# aeg_driver.net
KiCad netlist of a schematic drawn in EAGLE
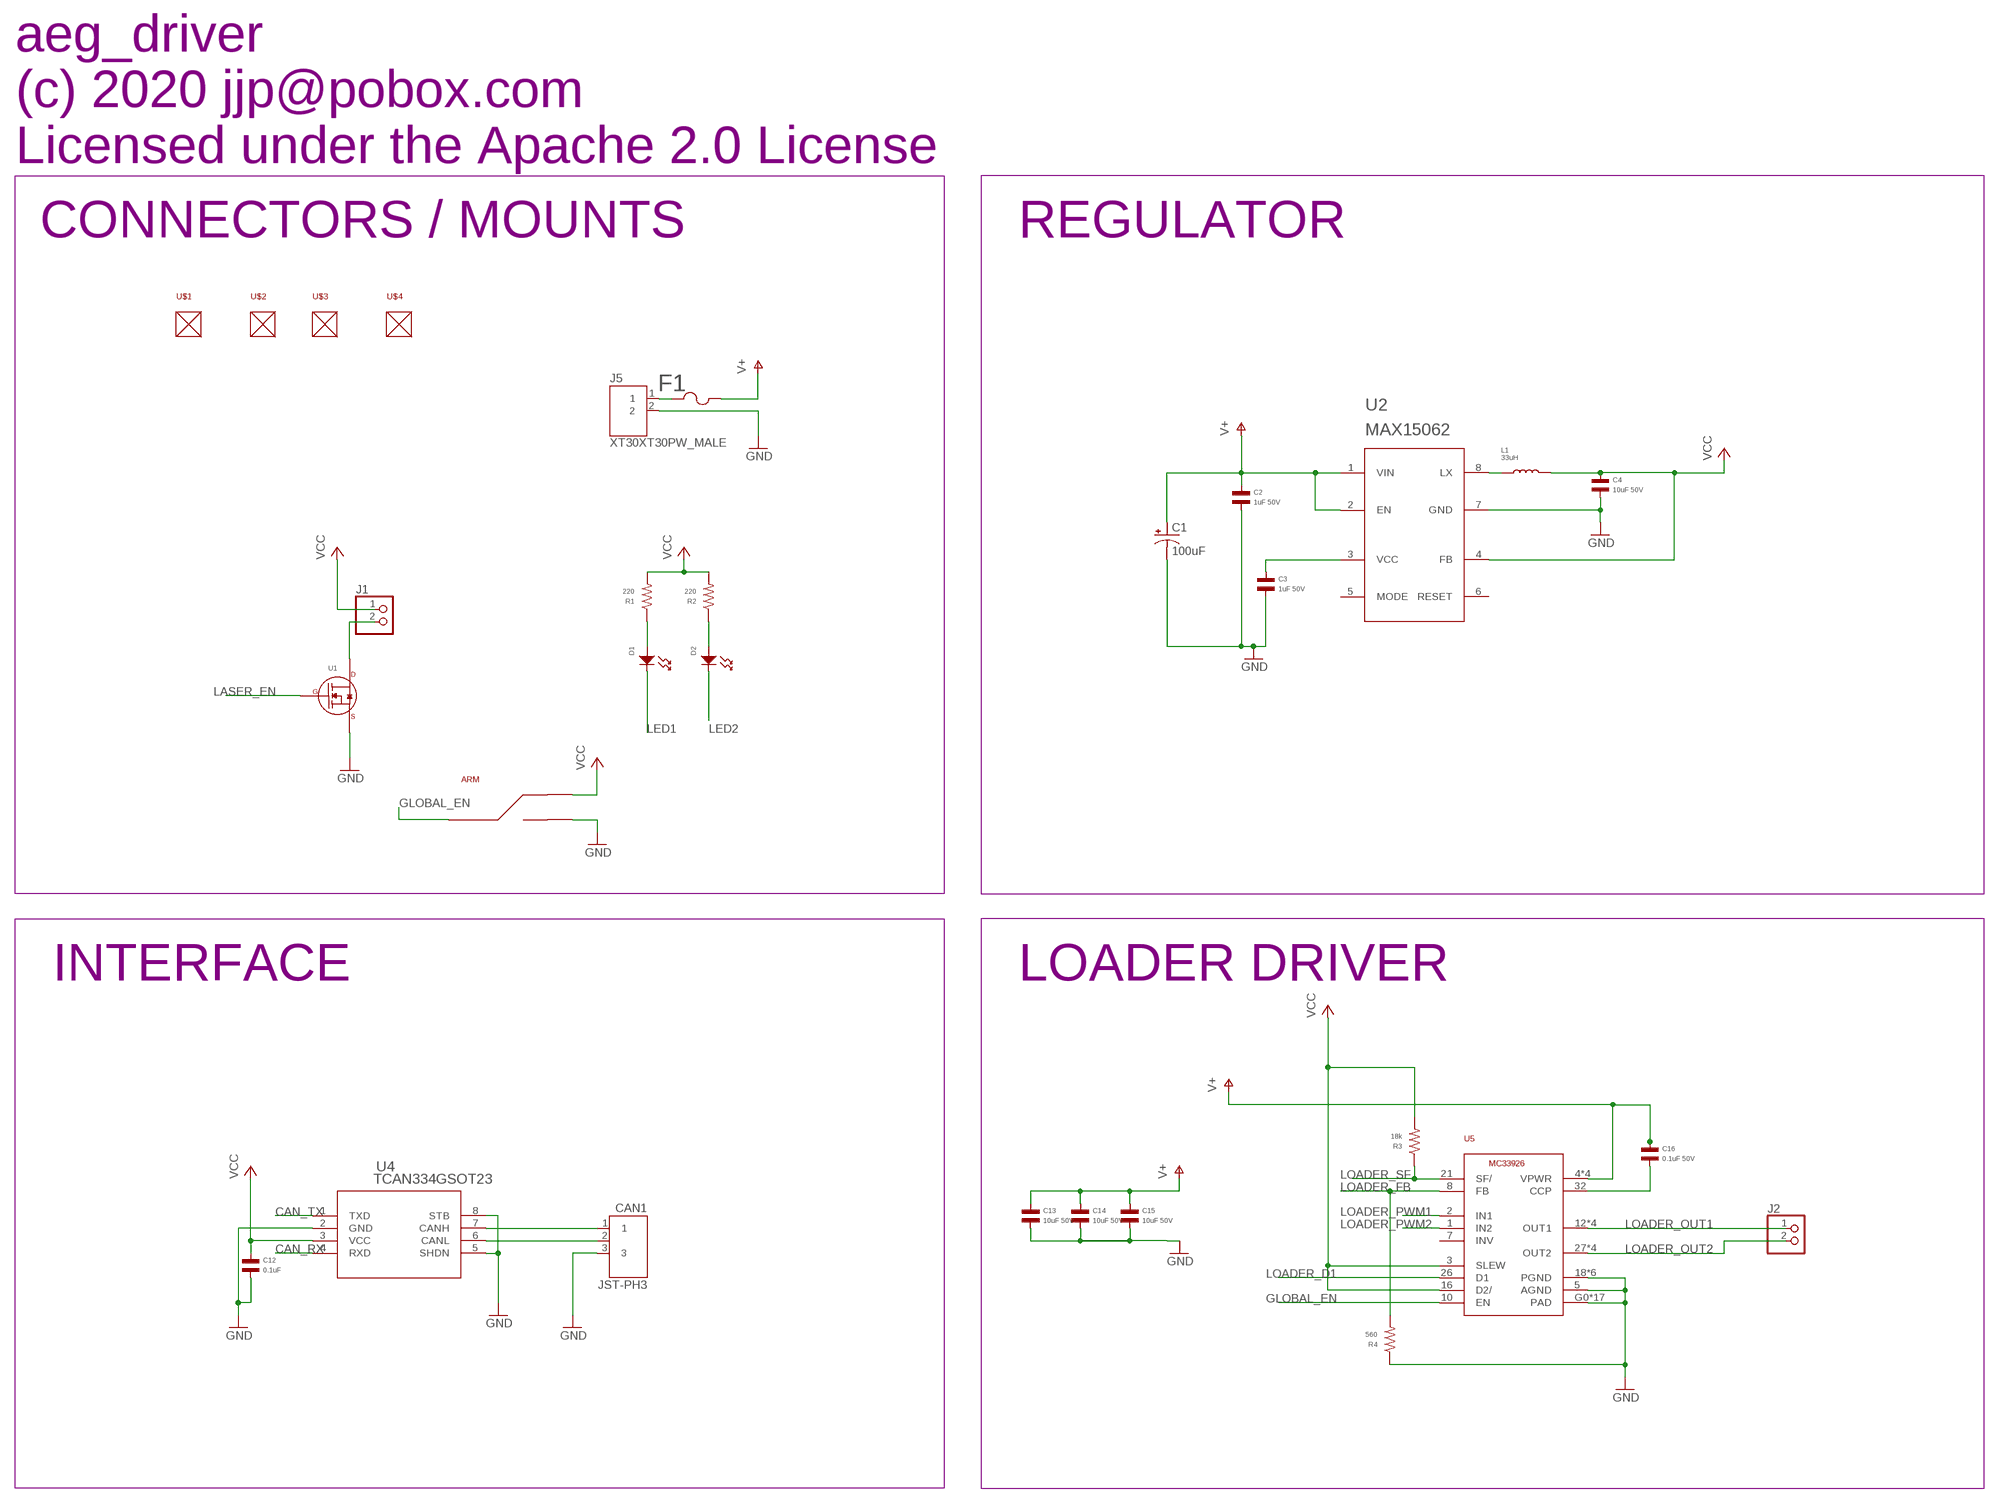
[diagram p0: schematic, sheet 1, part 1 of 2]
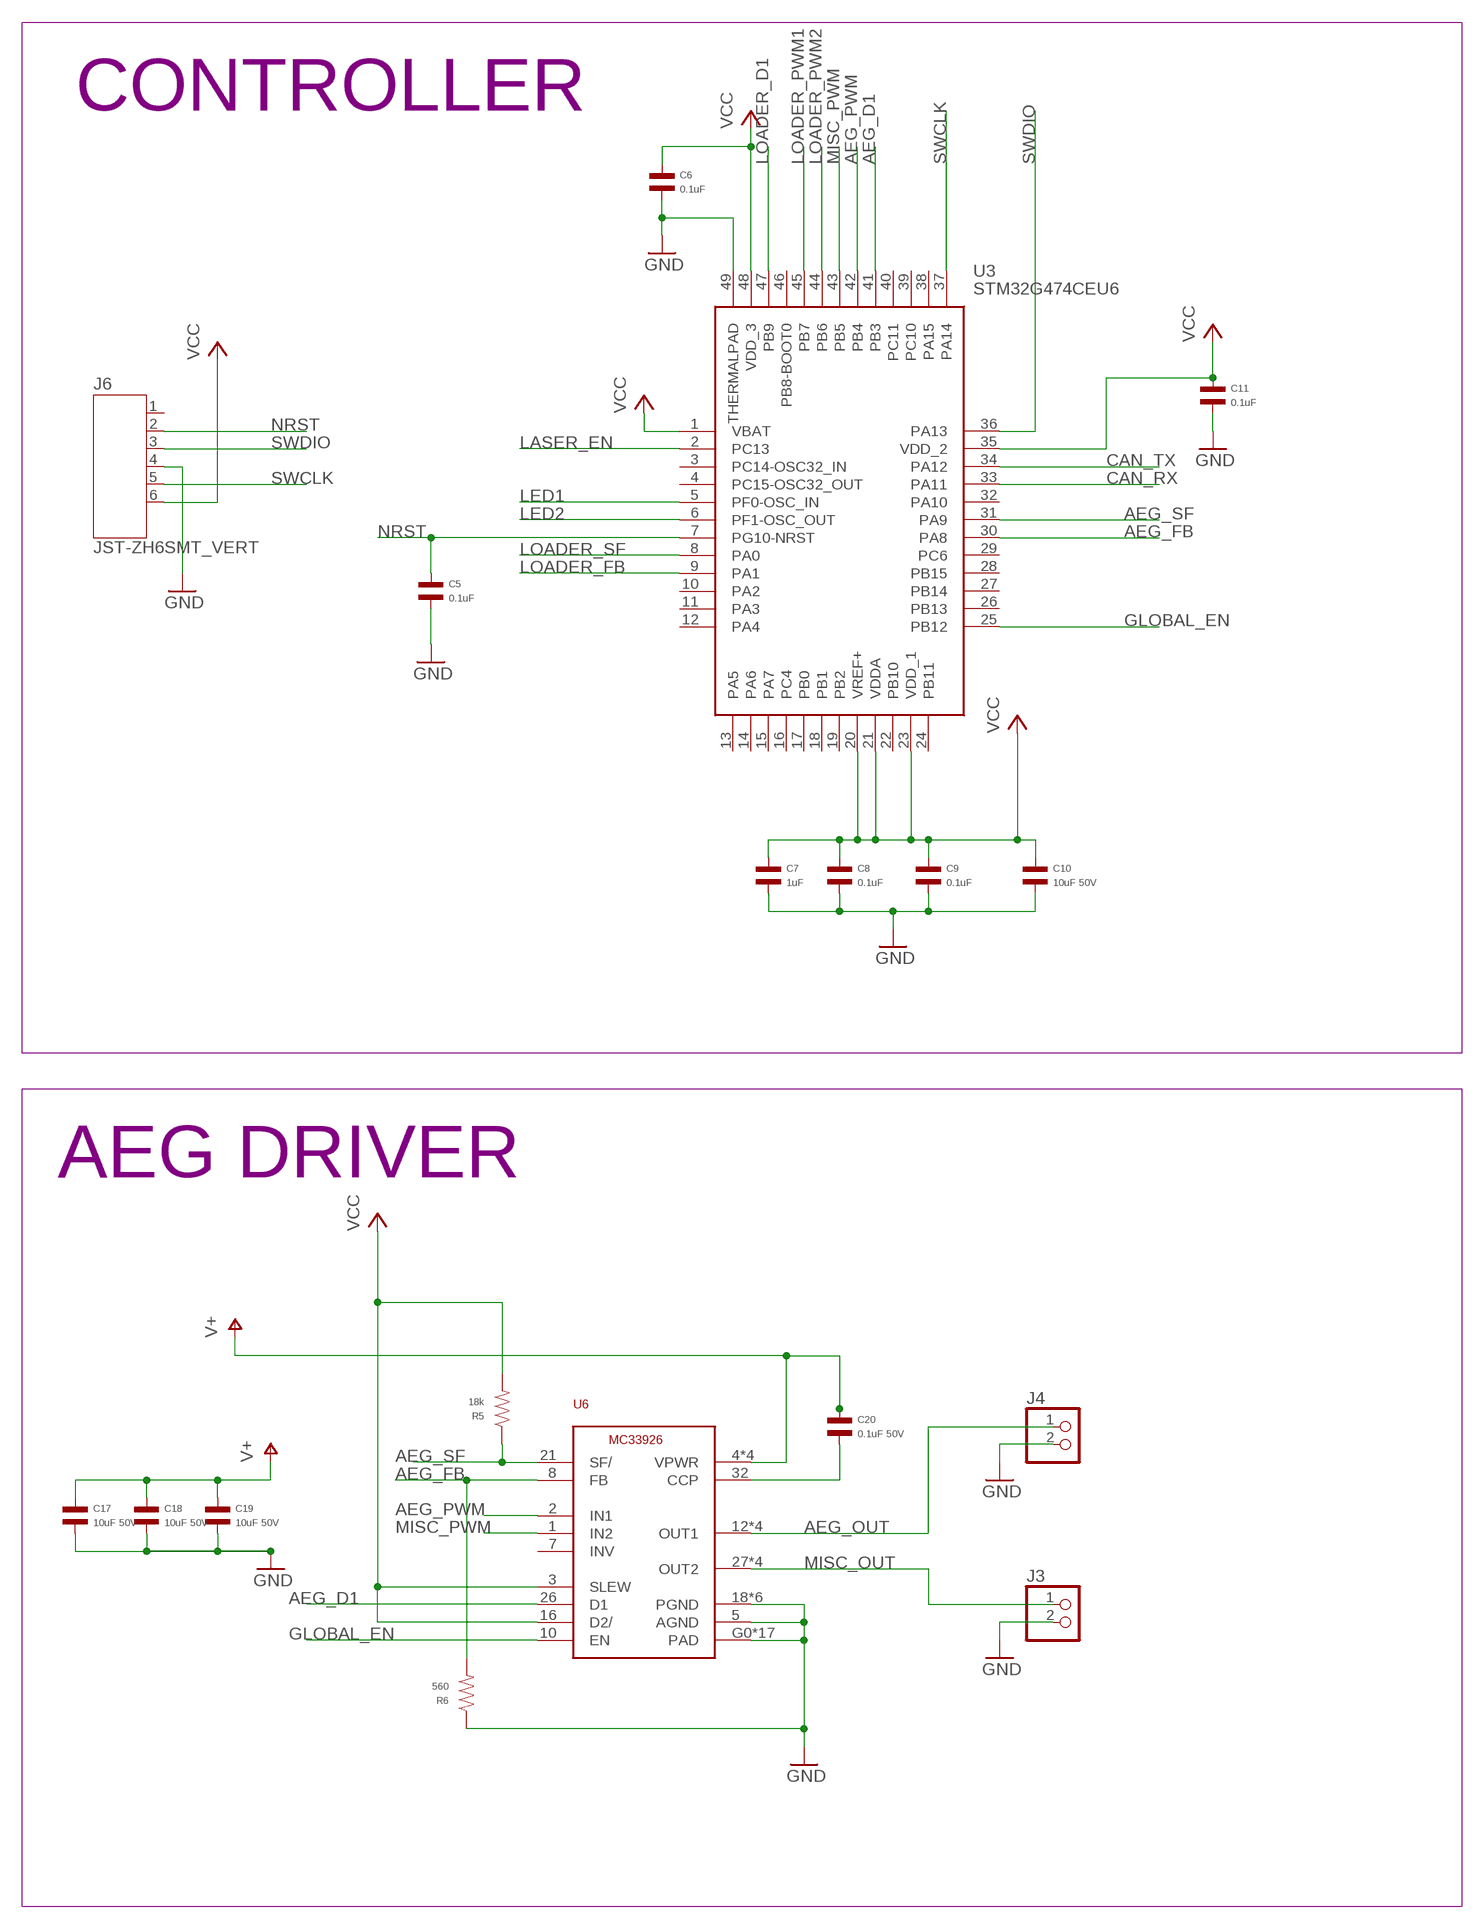
[diagram p1: schematic, sheet 1, part 2 of 2]

(export (version "E")
  (design (tool "Eeschema 10.0.6"))
  (components
    (comp (ref "ARM")
      (value "SLIDE_SWITCHJS_SUB_SWITCH")
      (footprint "eagle-import:JS_SUB_SWITCH")
      (fields (field (name "MPN") "JS102011SAQN"))
      (libsource (lib "eagle-import") (part "SLIDE_SWITCHJS_SUB_SWITCH"))
    )
    (comp (ref "C1")
      (value "100uF")
      (footprint "eagle-import:PANASONIC_FT_CAP_D")
      (fields (field (name "MF") "PANASONIC") (field (name "MPN") "EEE-FT1V101AP"))
      (libsource (lib "eagle-import") (part "CPOL-USFT_D"))
    )
    (comp (ref "C2")
      (value "1uF 50V")
      (footprint "eagle-import:C0603")
      (fields (field (name "MF") "SAMSUNG") (field (name "MPN") "CL10A105KB8NNNC"))
      (libsource (lib "eagle-import") (part "CAPACITOR_NP_0603"))
    )
    (comp (ref "C3")
      (value "1uF 50V")
      (footprint "eagle-import:C0603")
      (fields (field (name "MF") "SAMSUNG") (field (name "MPN") "CL10A105KB8NNNC"))
      (libsource (lib "eagle-import") (part "CAPACITOR_NP_0603"))
    )
    (comp (ref "C4")
      (value "10uF 50V")
      (footprint "eagle-import:C1206")
      (fields (field (name "MF") "TDK") (field (name "MPN") "C3216X7R1H106K160AE"))
      (libsource (lib "eagle-import") (part "CAPACITOR_NP_1206"))
    )
    (comp (ref "C5")
      (value "0.1uF")
      (footprint "eagle-import:C0402")
      (fields (field (name "HOUSEPART") "YES") (field (name "MPN") "MF-CAP-0402-0.1uF"))
      (libsource (lib "eagle-import") (part "CAPACITOR_NP_0402"))
    )
    (comp (ref "C6")
      (value "0.1uF")
      (footprint "eagle-import:C0402")
      (fields (field (name "HOUSEPART") "YES") (field (name "MPN") "MF-CAP-0402-0.1uF"))
      (libsource (lib "eagle-import") (part "CAPACITOR_NP_0402"))
    )
    (comp (ref "C7")
      (value "1uF")
      (footprint "eagle-import:C0402")
      (fields (field (name "HOUSEPART") "YES") (field (name "MPN") "MF-CAP-0402-1uF"))
      (libsource (lib "eagle-import") (part "CAPACITOR_NP_0402"))
    )
    (comp (ref "C8")
      (value "0.1uF")
      (footprint "eagle-import:C0402")
      (fields (field (name "HOUSEPART") "YES") (field (name "MPN") "MF-CAP-0402-0.1uF"))
      (libsource (lib "eagle-import") (part "CAPACITOR_NP_0402"))
    )
    (comp (ref "C9")
      (value "0.1uF")
      (footprint "eagle-import:C0402")
      (fields (field (name "HOUSEPART") "YES") (field (name "MPN") "MF-CAP-0402-0.1uF"))
      (libsource (lib "eagle-import") (part "CAPACITOR_NP_0402"))
    )
    (comp (ref "C10")
      (value "10uF 50V")
      (footprint "eagle-import:C1206")
      (fields (field (name "MF") "TDK") (field (name "MPN") "C3216X7R1H106K160AE"))
      (libsource (lib "eagle-import") (part "CAPACITOR_NP_1206"))
    )
    (comp (ref "C11")
      (value "0.1uF")
      (footprint "eagle-import:C0402")
      (fields (field (name "HOUSEPART") "YES") (field (name "MPN") "MF-CAP-0402-0.1uF"))
      (libsource (lib "eagle-import") (part "CAPACITOR_NP_0402"))
    )
    (comp (ref "C12")
      (value "0.1uF")
      (footprint "eagle-import:C0402")
      (fields (field (name "HOUSEPART") "YES") (field (name "MPN") "MF-CAP-0402-0.1uF"))
      (libsource (lib "eagle-import") (part "CAPACITOR_NP_0402"))
    )
    (comp (ref "C13")
      (value "10uF 50V")
      (footprint "eagle-import:C1206")
      (fields (field (name "MF") "TDK") (field (name "MPN") "C3216X7R1H106K160AE"))
      (libsource (lib "eagle-import") (part "CAPACITOR_NP_1206"))
    )
    (comp (ref "C14")
      (value "10uF 50V")
      (footprint "eagle-import:C1206")
      (fields (field (name "MF") "TDK") (field (name "MPN") "C3216X7R1H106K160AE"))
      (libsource (lib "eagle-import") (part "CAPACITOR_NP_1206"))
    )
    (comp (ref "C15")
      (value "10uF 50V")
      (footprint "eagle-import:C1206")
      (fields (field (name "MF") "TDK") (field (name "MPN") "C3216X7R1H106K160AE"))
      (libsource (lib "eagle-import") (part "CAPACITOR_NP_1206"))
    )
    (comp (ref "C16")
      (value "0.1uF 50V")
      (footprint "eagle-import:C0402")
      (fields (field (name "MF") "Walsin") (field (name "MPN") "0402B104K500CT"))
      (libsource (lib "eagle-import") (part "CAPACITOR_NP_0402"))
    )
    (comp (ref "C17")
      (value "10uF 50V")
      (footprint "eagle-import:C1206")
      (fields (field (name "MF") "TDK") (field (name "MPN") "C3216X7R1H106K160AE"))
      (libsource (lib "eagle-import") (part "CAPACITOR_NP_1206"))
    )
    (comp (ref "C18")
      (value "10uF 50V")
      (footprint "eagle-import:C1206")
      (fields (field (name "MF") "TDK") (field (name "MPN") "C3216X7R1H106K160AE"))
      (libsource (lib "eagle-import") (part "CAPACITOR_NP_1206"))
    )
    (comp (ref "C19")
      (value "10uF 50V")
      (footprint "eagle-import:C1206")
      (fields (field (name "MF") "TDK") (field (name "MPN") "C3216X7R1H106K160AE"))
      (libsource (lib "eagle-import") (part "CAPACITOR_NP_1206"))
    )
    (comp (ref "C20")
      (value "0.1uF 50V")
      (footprint "eagle-import:C0402")
      (fields (field (name "MF") "Walsin") (field (name "MPN") "0402B104K500CT"))
      (libsource (lib "eagle-import") (part "CAPACITOR_NP_0402"))
    )
    (comp (ref "CAN1")
      (value "JST-PH3")
      (footprint "eagle-import:JST_S3B-PH-SM4-TB(LF)(SN)")
      (fields (field (name "MF") "JST") (field (name "MPN") "S3B-PH-SM4-TB(LF)(SN)"))
      (libsource (lib "eagle-import") (part "JST-PH3"))
    )
    (comp (ref "D1")
      (value "LED_SINGLE-0603-RED")
      (footprint "eagle-import:LED0603")
      (fields (field (name "HOUSEPART") "YES") (field (name "MPN") "MF-LED-0603-RED"))
      (libsource (lib "eagle-import") (part "LED_SINGLE-0603-RED"))
    )
    (comp (ref "D2")
      (value "LED_SINGLE-0603-RED")
      (footprint "eagle-import:LED0603")
      (fields
        (field (name "HOUSEPART") "YES")
        (field (name "MPN") "MF-LED-0603-RED")
        (field (name "MPN_1") "MF-LED-0603-GREEN")
      )
      (libsource (lib "eagle-import") (part "LED_SINGLE-0603-RED"))
    )
    (comp (ref "F1")
      (value "MFU0603FF04000P100")
      (footprint "eagle-import:FUS_VISHAY_MFU0603")
      (fields (field (name "MF") "VISHAY"))
      (libsource (lib "eagle-import") (part "MFU0603FF04000P100"))
    )
    (comp (ref "J1")
      (value "PINHD-1X2")
      (footprint "eagle-import:1X02")
      (libsource (lib "eagle-import") (part "PINHD-1X2"))
    )
    (comp (ref "J2")
      (value "PINHD-1X2")
      (footprint "eagle-import:1X02")
      (libsource (lib "eagle-import") (part "PINHD-1X2"))
    )
    (comp (ref "J3")
      (value "PINHD-1X2")
      (footprint "eagle-import:1X02")
      (libsource (lib "eagle-import") (part "PINHD-1X2"))
    )
    (comp (ref "J4")
      (value "PINHD-1X2")
      (footprint "eagle-import:1X02")
      (libsource (lib "eagle-import") (part "PINHD-1X2"))
    )
    (comp (ref "J5")
      (value "XT30XT30PW_MALE")
      (footprint "eagle-import:XT30PW_MALE")
      (fields (field (name "MPN") "XT30PW-M"))
      (libsource (lib "eagle-import") (part "XT30XT30PW_MALE"))
    )
    (comp (ref "J6")
      (value "JST-ZH6SMT_VERT")
      (footprint "eagle-import:JST_B6B-ZR-SM4-TF(LF)(SN)")
      (fields (field (name "MF") "JST") (field (name "MPN") "B6B-ZR-SM4-TF(LF)(SN)"))
      (libsource (lib "eagle-import") (part "JST-ZH6SMT_VERT"))
    )
    (comp (ref "L1")
      (value "33uH")
      (footprint "eagle-import:L1210")
      (fields (field (name "MF") "TDK") (field (name "MPN") "NLFV32T-330K-EF") (field (name "POPULATE") "1"))
      (libsource (lib "eagle-import") (part "INDUCTOR_1210"))
    )
    (comp (ref "R1")
      (value "220")
      (footprint "eagle-import:R0603")
      (fields (field (name "HOUSEPART") "YES") (field (name "MPN") "MF-RES-0603-220"))
      (libsource (lib "eagle-import") (part "RESISTOR_0603"))
    )
    (comp (ref "R2")
      (value "220")
      (footprint "eagle-import:R0603")
      (fields (field (name "HOUSEPART") "YES") (field (name "MPN") "MF-RES-0603-220"))
      (libsource (lib "eagle-import") (part "RESISTOR_0603"))
    )
    (comp (ref "R3")
      (value "18k")
      (footprint "eagle-import:R0603")
      (fields (field (name "HOUSEPART") "YES") (field (name "MPN") "MF-RES-0603-18K"))
      (libsource (lib "eagle-import") (part "RESISTOR_0603"))
    )
    (comp (ref "R4")
      (value "560")
      (footprint "eagle-import:R0603")
      (fields (field (name "HOUSEPART") "YES") (field (name "MPN") "MF-RES-0603-560"))
      (libsource (lib "eagle-import") (part "RESISTOR_0603"))
    )
    (comp (ref "R5")
      (value "18k")
      (footprint "eagle-import:R0603")
      (fields (field (name "HOUSEPART") "YES") (field (name "MPN") "MF-RES-0603-18K"))
      (libsource (lib "eagle-import") (part "RESISTOR_0603"))
    )
    (comp (ref "R6")
      (value "560")
      (footprint "eagle-import:R0603")
      (fields (field (name "HOUSEPART") "YES") (field (name "MPN") "MF-RES-0603-560"))
      (libsource (lib "eagle-import") (part "RESISTOR_0603"))
    )
    (comp (ref "U$1")
      (value "MOUNT")
      (footprint "eagle-import:M2.5MOUNT")
      (libsource (lib "eagle-import") (part "MOUNT"))
    )
    (comp (ref "U$2")
      (value "MOUNT")
      (footprint "eagle-import:M2.5MOUNT")
      (libsource (lib "eagle-import") (part "MOUNT"))
    )
    (comp (ref "U$3")
      (value "MOUNT")
      (footprint "eagle-import:M2.5MOUNT")
      (libsource (lib "eagle-import") (part "MOUNT"))
    )
    (comp (ref "U$4")
      (value "MOUNT")
      (footprint "eagle-import:M2.5MOUNT")
      (libsource (lib "eagle-import") (part "MOUNT"))
    )
    (comp (ref "U1")
      (value "N-CHANNEL_FET_SOT-23-3")
      (footprint "eagle-import:SOT-23-3")
      (fields (field (name "HOUSEPART") "YES") (field (name "MPN") "MF-DSC-SOT233-BSS138"))
      (libsource (lib "eagle-import") (part "N-CHANNEL_FET_SOT-23-3"))
    )
    (comp (ref "U2")
      (value "MAX150628TDFN")
      (footprint "eagle-import:8TDFN")
      (fields (field (name "MF") "MAXIM") (field (name "MPN") "MAX15062AATA+T"))
      (libsource (lib "eagle-import") (part "MAX150628TDFN"))
    )
    (comp (ref "U3")
      (value "STM32G474CEU6")
      (footprint "eagle-import:QFN50P700X700X60-49N")
      (fields (field (name "MOUSER_PART_NUMBER") "511-STM32G474CEU6") (field (name "MF") "ST"))
      (libsource (lib "eagle-import") (part "STM32G474CEU6"))
    )
    (comp (ref "U4")
      (value "TCAN334GSOT23")
      (footprint "eagle-import:SOT23-8")
      (fields (field (name "MF") "TI") (field (name "MPN") "TCAN334GDCNT"))
      (libsource (lib "eagle-import") (part "TCAN334GSOT23"))
    )
    (comp (ref "U5")
      (value "MC33926")
      (footprint "eagle-import:PQFN32")
      (fields (field (name "MF") "Freescale") (field (name "MPN") "MC33926PNBR2"))
      (libsource (lib "eagle-import") (part "MC33926"))
    )
    (comp (ref "U6")
      (value "MC33926")
      (footprint "eagle-import:PQFN32")
      (fields (field (name "MF") "Freescale") (field (name "MPN") "MC33926PNBR2"))
      (libsource (lib "eagle-import") (part "MC33926"))
    )
  )
  (nets
    (net (code "1") (name "/AEG_D1") (class "Default")
      (node (ref "U3") (pin "41") (pinfunction "PB3_41") (pintype "bidirectional"))
      (node (ref "U6") (pin "26") (pinfunction "D1_26") (pintype "bidirectional"))
    )
    (net (code "2") (name "/AEG_FB") (class "Default")
      (node (ref "R6") (pin "P$2") (pinfunction "P$2_P$2") (pintype "passive"))
      (node (ref "U3") (pin "30") (pinfunction "PA8_30") (pintype "bidirectional"))
      (node (ref "U6") (pin "8") (pinfunction "FB_8") (pintype "bidirectional"))
    )
    (net (code "3") (name "/AEG_OUT") (class "Default")
      (node (ref "J4") (pin "1") (pinfunction "1_1") (pintype "passive"))
      (node (ref "U6") (pin "12") (pinfunction "OUT1_12") (pintype "bidirectional"))
      (node (ref "U6") (pin "13") (pinfunction "OUT1_13") (pintype "bidirectional"))
      (node (ref "U6") (pin "14") (pinfunction "OUT1_14") (pintype "bidirectional"))
      (node (ref "U6") (pin "15") (pinfunction "OUT1_15") (pintype "bidirectional"))
    )
    (net (code "4") (name "/AEG_PWM") (class "Default")
      (node (ref "U3") (pin "42") (pinfunction "PB4_42") (pintype "bidirectional"))
      (node (ref "U6") (pin "2") (pinfunction "IN1_2") (pintype "bidirectional"))
    )
    (net (code "5") (name "/AEG_SF") (class "Default")
      (node (ref "R5") (pin "P$1") (pinfunction "P$1_P$1") (pintype "passive"))
      (node (ref "U3") (pin "31") (pinfunction "PA9_31") (pintype "bidirectional"))
      (node (ref "U6") (pin "21") (pinfunction "SF/_21") (pintype "bidirectional"))
    )
    (net (code "6") (name "/CAN_RX") (class "Default")
      (node (ref "U3") (pin "33") (pinfunction "PA11_33") (pintype "bidirectional"))
      (node (ref "U4") (pin "4") (pinfunction "RXD_4") (pintype "output"))
    )
    (net (code "7") (name "/CAN_TX") (class "Default")
      (node (ref "U3") (pin "34") (pinfunction "PA12_34") (pintype "bidirectional"))
      (node (ref "U4") (pin "1") (pinfunction "TXD_1") (pintype "input"))
    )
    (net (code "8") (name "/GLOBAL_EN") (class "Default")
      (node (ref "ARM") (pin "2") (pinfunction "2_2") (pintype "bidirectional"))
      (node (ref "U3") (pin "25") (pinfunction "PB12_25") (pintype "bidirectional"))
      (node (ref "U5") (pin "10") (pinfunction "EN_10") (pintype "bidirectional"))
      (node (ref "U6") (pin "10") (pinfunction "EN_10") (pintype "bidirectional"))
    )
    (net (code "9") (name "/LASER_EN") (class "Default")
      (node (ref "U1") (pin "P$1") (pinfunction "GATE_P$1") (pintype "bidirectional"))
      (node (ref "U3") (pin "2") (pinfunction "PC13_2") (pintype "bidirectional"))
    )
    (net (code "10") (name "/LED1") (class "Default")
      (node (ref "D1") (pin "CATHODE") (pinfunction "CATHODE_CATHODE") (pintype "power_in"))
      (node (ref "U3") (pin "5") (pinfunction "PF0-OSC_IN_5") (pintype "bidirectional"))
    )
    (net (code "11") (name "/LED2") (class "Default")
      (node (ref "D2") (pin "CATHODE") (pinfunction "CATHODE_CATHODE") (pintype "power_in"))
      (node (ref "U3") (pin "6") (pinfunction "PF1-OSC_OUT_6") (pintype "bidirectional"))
    )
    (net (code "12") (name "/LOADER_D1") (class "Default")
      (node (ref "U3") (pin "47") (pinfunction "PB9_47") (pintype "bidirectional"))
      (node (ref "U5") (pin "26") (pinfunction "D1_26") (pintype "bidirectional"))
    )
    (net (code "13") (name "/LOADER_FB") (class "Default")
      (node (ref "R4") (pin "P$2") (pinfunction "P$2_P$2") (pintype "passive"))
      (node (ref "U3") (pin "9") (pinfunction "PA1_9") (pintype "bidirectional"))
      (node (ref "U5") (pin "8") (pinfunction "FB_8") (pintype "bidirectional"))
    )
    (net (code "14") (name "/LOADER_OUT1") (class "Default")
      (node (ref "J2") (pin "1") (pinfunction "1_1") (pintype "passive"))
      (node (ref "U5") (pin "12") (pinfunction "OUT1_12") (pintype "bidirectional"))
      (node (ref "U5") (pin "13") (pinfunction "OUT1_13") (pintype "bidirectional"))
      (node (ref "U5") (pin "14") (pinfunction "OUT1_14") (pintype "bidirectional"))
      (node (ref "U5") (pin "15") (pinfunction "OUT1_15") (pintype "bidirectional"))
    )
    (net (code "15") (name "/LOADER_OUT2") (class "Default")
      (node (ref "J2") (pin "2") (pinfunction "2_2") (pintype "passive"))
      (node (ref "U5") (pin "27") (pinfunction "OUT2_27") (pintype "bidirectional"))
      (node (ref "U5") (pin "28") (pinfunction "OUT2_28") (pintype "bidirectional"))
      (node (ref "U5") (pin "29") (pinfunction "OUT2_29") (pintype "bidirectional"))
      (node (ref "U5") (pin "30") (pinfunction "OUT2_30") (pintype "bidirectional"))
    )
    (net (code "16") (name "/LOADER_PWM1") (class "Default")
      (node (ref "U3") (pin "45") (pinfunction "PB7_45") (pintype "bidirectional"))
      (node (ref "U5") (pin "2") (pinfunction "IN1_2") (pintype "bidirectional"))
    )
    (net (code "17") (name "/LOADER_PWM2") (class "Default")
      (node (ref "U3") (pin "44") (pinfunction "PB6_44") (pintype "bidirectional"))
      (node (ref "U5") (pin "1") (pinfunction "IN2_1") (pintype "bidirectional"))
    )
    (net (code "18") (name "/LOADER_SF") (class "Default")
      (node (ref "R3") (pin "P$1") (pinfunction "P$1_P$1") (pintype "passive"))
      (node (ref "U3") (pin "8") (pinfunction "PA0_8") (pintype "bidirectional"))
      (node (ref "U5") (pin "21") (pinfunction "SF/_21") (pintype "bidirectional"))
    )
    (net (code "19") (name "/MISC_OUT") (class "Default")
      (node (ref "J3") (pin "1") (pinfunction "1_1") (pintype "passive"))
      (node (ref "U6") (pin "27") (pinfunction "OUT2_27") (pintype "bidirectional"))
      (node (ref "U6") (pin "28") (pinfunction "OUT2_28") (pintype "bidirectional"))
      (node (ref "U6") (pin "29") (pinfunction "OUT2_29") (pintype "bidirectional"))
      (node (ref "U6") (pin "30") (pinfunction "OUT2_30") (pintype "bidirectional"))
    )
    (net (code "20") (name "/MISC_PWM") (class "Default")
      (node (ref "U3") (pin "43") (pinfunction "PB5_43") (pintype "bidirectional"))
      (node (ref "U6") (pin "1") (pinfunction "IN2_1") (pintype "bidirectional"))
    )
    (net (code "21") (name "/NRST") (class "Default")
      (node (ref "C5") (pin "P$1") (pinfunction "P$1_P$1") (pintype "passive"))
      (node (ref "J6") (pin "2") (pinfunction "2_2") (pintype "passive"))
      (node (ref "U3") (pin "7") (pinfunction "PG10-NRST_7") (pintype "bidirectional"))
    )
    (net (code "22") (name "/SWCLK") (class "Default")
      (node (ref "J6") (pin "5") (pinfunction "5_5") (pintype "passive"))
      (node (ref "U3") (pin "37") (pinfunction "PA14_37") (pintype "bidirectional"))
    )
    (net (code "23") (name "/SWDIO") (class "Default")
      (node (ref "J6") (pin "3") (pinfunction "3_3") (pintype "passive"))
      (node (ref "U3") (pin "36") (pinfunction "PA13_36") (pintype "bidirectional"))
    )
    (net (code "24") (name "GND") (class "Default")
      (node (ref "ARM") (pin "3") (pinfunction "3_3") (pintype "bidirectional"))
      (node (ref "C1") (pin "-") (pinfunction "-_-") (pintype "passive"))
      (node (ref "C10") (pin "P$2") (pinfunction "P$2_P$2") (pintype "passive"))
      (node (ref "C11") (pin "P$2") (pinfunction "P$2_P$2") (pintype "passive"))
      (node (ref "C12") (pin "P$2") (pinfunction "P$2_P$2") (pintype "passive"))
      (node (ref "C13") (pin "P$2") (pinfunction "P$2_P$2") (pintype "passive"))
      (node (ref "C14") (pin "P$2") (pinfunction "P$2_P$2") (pintype "passive"))
      (node (ref "C15") (pin "P$2") (pinfunction "P$2_P$2") (pintype "passive"))
      (node (ref "C17") (pin "P$2") (pinfunction "P$2_P$2") (pintype "passive"))
      (node (ref "C18") (pin "P$2") (pinfunction "P$2_P$2") (pintype "passive"))
      (node (ref "C19") (pin "P$2") (pinfunction "P$2_P$2") (pintype "passive"))
      (node (ref "C2") (pin "P$2") (pinfunction "P$2_P$2") (pintype "passive"))
      (node (ref "C3") (pin "P$2") (pinfunction "P$2_P$2") (pintype "passive"))
      (node (ref "C4") (pin "P$2") (pinfunction "P$2_P$2") (pintype "passive"))
      (node (ref "C5") (pin "P$2") (pinfunction "P$2_P$2") (pintype "passive"))
      (node (ref "C6") (pin "P$2") (pinfunction "P$2_P$2") (pintype "passive"))
      (node (ref "C7") (pin "P$2") (pinfunction "P$2_P$2") (pintype "passive"))
      (node (ref "C8") (pin "P$2") (pinfunction "P$2_P$2") (pintype "passive"))
      (node (ref "C9") (pin "P$2") (pinfunction "P$2_P$2") (pintype "passive"))
      (node (ref "CAN1") (pin "3") (pinfunction "3_3") (pintype "passive"))
      (node (ref "J3") (pin "2") (pinfunction "2_2") (pintype "passive"))
      (node (ref "J4") (pin "2") (pinfunction "2_2") (pintype "passive"))
      (node (ref "J5") (pin "2") (pinfunction "2_2") (pintype "passive"))
      (node (ref "J6") (pin "4") (pinfunction "4_4") (pintype "passive"))
      (node (ref "R4") (pin "P$1") (pinfunction "P$1_P$1") (pintype "passive"))
      (node (ref "R6") (pin "P$1") (pinfunction "P$1_P$1") (pintype "passive"))
      (node (ref "U1") (pin "P$2") (pinfunction "SOURCE_P$2") (pintype "bidirectional"))
      (node (ref "U2") (pin "7") (pinfunction "GND_7") (pintype "passive"))
      (node (ref "U3") (pin "49") (pinfunction "THERMALPAD_49") (pintype "bidirectional"))
      (node (ref "U4") (pin "2") (pinfunction "GND_2") (pintype "power_in"))
      (node (ref "U4") (pin "5") (pinfunction "SHDN_5") (pintype "input"))
      (node (ref "U4") (pin "8") (pinfunction "STB_8") (pintype "input"))
      (node (ref "U5") (pin "18") (pinfunction "PGND_18") (pintype "bidirectional"))
      (node (ref "U5") (pin "19") (pinfunction "PGND_19") (pintype "bidirectional"))
      (node (ref "U5") (pin "20") (pinfunction "PGND_20") (pintype "bidirectional"))
      (node (ref "U5") (pin "22") (pinfunction "PGND_22") (pintype "bidirectional"))
      (node (ref "U5") (pin "23") (pinfunction "PGND_23") (pintype "bidirectional"))
      (node (ref "U5") (pin "24") (pinfunction "PGND_24") (pintype "bidirectional"))
      (node (ref "U5") (pin "5") (pinfunction "AGND_5") (pintype "bidirectional"))
      (node (ref "U5") (pin "G0") (pinfunction "PAD_G0") (pintype "bidirectional"))
      (node (ref "U5") (pin "G1") (pinfunction "PAD_G1") (pintype "bidirectional"))
      (node (ref "U5") (pin "G10") (pinfunction "PAD_G10") (pintype "bidirectional"))
      (node (ref "U5") (pin "G11") (pinfunction "PAD_G11") (pintype "bidirectional"))
      (node (ref "U5") (pin "G12") (pinfunction "PAD_G12") (pintype "bidirectional"))
      (node (ref "U5") (pin "G13") (pinfunction "PAD_G13") (pintype "bidirectional"))
      (node (ref "U5") (pin "G14") (pinfunction "PAD_G14") (pintype "bidirectional"))
      (node (ref "U5") (pin "G15") (pinfunction "PAD_G15") (pintype "bidirectional"))
      (node (ref "U5") (pin "G16") (pinfunction "PAD_G16") (pintype "bidirectional"))
      (node (ref "U5") (pin "G2") (pinfunction "PAD_G2") (pintype "bidirectional"))
      (node (ref "U5") (pin "G3") (pinfunction "PAD_G3") (pintype "bidirectional"))
      (node (ref "U5") (pin "G4") (pinfunction "PAD_G4") (pintype "bidirectional"))
      (node (ref "U5") (pin "G5") (pinfunction "PAD_G5") (pintype "bidirectional"))
      (node (ref "U5") (pin "G6") (pinfunction "PAD_G6") (pintype "bidirectional"))
      (node (ref "U5") (pin "G7") (pinfunction "PAD_G7") (pintype "bidirectional"))
      (node (ref "U5") (pin "G8") (pinfunction "PAD_G8") (pintype "bidirectional"))
      (node (ref "U5") (pin "G9") (pinfunction "PAD_G9") (pintype "bidirectional"))
      (node (ref "U6") (pin "18") (pinfunction "PGND_18") (pintype "bidirectional"))
      (node (ref "U6") (pin "19") (pinfunction "PGND_19") (pintype "bidirectional"))
      (node (ref "U6") (pin "20") (pinfunction "PGND_20") (pintype "bidirectional"))
      (node (ref "U6") (pin "22") (pinfunction "PGND_22") (pintype "bidirectional"))
      (node (ref "U6") (pin "23") (pinfunction "PGND_23") (pintype "bidirectional"))
      (node (ref "U6") (pin "24") (pinfunction "PGND_24") (pintype "bidirectional"))
      (node (ref "U6") (pin "5") (pinfunction "AGND_5") (pintype "bidirectional"))
      (node (ref "U6") (pin "G0") (pinfunction "PAD_G0") (pintype "bidirectional"))
      (node (ref "U6") (pin "G1") (pinfunction "PAD_G1") (pintype "bidirectional"))
      (node (ref "U6") (pin "G10") (pinfunction "PAD_G10") (pintype "bidirectional"))
      (node (ref "U6") (pin "G11") (pinfunction "PAD_G11") (pintype "bidirectional"))
      (node (ref "U6") (pin "G12") (pinfunction "PAD_G12") (pintype "bidirectional"))
      (node (ref "U6") (pin "G13") (pinfunction "PAD_G13") (pintype "bidirectional"))
      (node (ref "U6") (pin "G14") (pinfunction "PAD_G14") (pintype "bidirectional"))
      (node (ref "U6") (pin "G15") (pinfunction "PAD_G15") (pintype "bidirectional"))
      (node (ref "U6") (pin "G16") (pinfunction "PAD_G16") (pintype "bidirectional"))
      (node (ref "U6") (pin "G2") (pinfunction "PAD_G2") (pintype "bidirectional"))
      (node (ref "U6") (pin "G3") (pinfunction "PAD_G3") (pintype "bidirectional"))
      (node (ref "U6") (pin "G4") (pinfunction "PAD_G4") (pintype "bidirectional"))
      (node (ref "U6") (pin "G5") (pinfunction "PAD_G5") (pintype "bidirectional"))
      (node (ref "U6") (pin "G6") (pinfunction "PAD_G6") (pintype "bidirectional"))
      (node (ref "U6") (pin "G7") (pinfunction "PAD_G7") (pintype "bidirectional"))
      (node (ref "U6") (pin "G8") (pinfunction "PAD_G8") (pintype "bidirectional"))
      (node (ref "U6") (pin "G9") (pinfunction "PAD_G9") (pintype "bidirectional"))
    )
    (net (code "25") (name "Net-(D1-PadANODE)") (class "Default")
      (node (ref "D1") (pin "ANODE") (pinfunction "ANODE_ANODE") (pintype "power_in"))
      (node (ref "R1") (pin "P$1") (pinfunction "P$1_P$1") (pintype "passive"))
    )
    (net (code "26") (name "Net-(D2-PadANODE)") (class "Default")
      (node (ref "D2") (pin "ANODE") (pinfunction "ANODE_ANODE") (pintype "power_in"))
      (node (ref "R2") (pin "P$1") (pinfunction "P$1_P$1") (pintype "passive"))
    )
    (net (code "27") (name "Net-(F1-Pad1)") (class "Default")
      (node (ref "F1") (pin "1") (pinfunction "1_1") (pintype "passive"))
      (node (ref "J5") (pin "1") (pinfunction "1_1") (pintype "passive"))
    )
    (net (code "28") (name "Net-(U1-DRAIN)") (class "Default")
      (node (ref "J1") (pin "2") (pinfunction "2_2") (pintype "passive"))
      (node (ref "U1") (pin "P$3") (pinfunction "DRAIN_P$3") (pintype "bidirectional"))
    )
    (net (code "29") (name "Net-(U2-LX)") (class "Default")
      (node (ref "L1") (pin "P$1") (pinfunction "P$1_P$1") (pintype "passive"))
      (node (ref "U2") (pin "8") (pinfunction "LX_8") (pintype "passive"))
    )
    (net (code "30") (name "Net-(U2-VCC)") (class "Default")
      (node (ref "C3") (pin "P$1") (pinfunction "P$1_P$1") (pintype "passive"))
      (node (ref "U2") (pin "3") (pinfunction "VCC_3") (pintype "passive"))
    )
    (net (code "31") (name "Net-(U4-CANH)") (class "Default")
      (node (ref "CAN1") (pin "1") (pinfunction "1_1") (pintype "passive"))
      (node (ref "U4") (pin "7") (pinfunction "CANH_7") (pintype "bidirectional"))
    )
    (net (code "32") (name "Net-(U4-CANL)") (class "Default")
      (node (ref "CAN1") (pin "2") (pinfunction "2_2") (pintype "passive"))
      (node (ref "U4") (pin "6") (pinfunction "CANL_6") (pintype "bidirectional"))
    )
    (net (code "33") (name "Net-(U5-CCP)") (class "Default")
      (node (ref "C16") (pin "P$2") (pinfunction "P$2_P$2") (pintype "passive"))
      (node (ref "U5") (pin "32") (pinfunction "CCP_32") (pintype "bidirectional"))
    )
    (net (code "34") (name "Net-(U6-CCP)") (class "Default")
      (node (ref "C20") (pin "P$2") (pinfunction "P$2_P$2") (pintype "passive"))
      (node (ref "U6") (pin "32") (pinfunction "CCP_32") (pintype "bidirectional"))
    )
    (net (code "35") (name "V+") (class "Default")
      (node (ref "C1") (pin "+") (pinfunction "+_+") (pintype "passive"))
      (node (ref "C13") (pin "P$1") (pinfunction "P$1_P$1") (pintype "passive"))
      (node (ref "C14") (pin "P$1") (pinfunction "P$1_P$1") (pintype "passive"))
      (node (ref "C15") (pin "P$1") (pinfunction "P$1_P$1") (pintype "passive"))
      (node (ref "C16") (pin "P$1") (pinfunction "P$1_P$1") (pintype "passive"))
      (node (ref "C17") (pin "P$1") (pinfunction "P$1_P$1") (pintype "passive"))
      (node (ref "C18") (pin "P$1") (pinfunction "P$1_P$1") (pintype "passive"))
      (node (ref "C19") (pin "P$1") (pinfunction "P$1_P$1") (pintype "passive"))
      (node (ref "C2") (pin "P$1") (pinfunction "P$1_P$1") (pintype "passive"))
      (node (ref "C20") (pin "P$1") (pinfunction "P$1_P$1") (pintype "passive"))
      (node (ref "F1") (pin "2") (pinfunction "2_2") (pintype "passive"))
      (node (ref "U2") (pin "1") (pinfunction "VIN_1") (pintype "passive"))
      (node (ref "U2") (pin "2") (pinfunction "EN_2") (pintype "passive"))
      (node (ref "U5") (pin "11") (pinfunction "VPWR_11") (pintype "bidirectional"))
      (node (ref "U5") (pin "31") (pinfunction "VPWR_31") (pintype "bidirectional"))
      (node (ref "U5") (pin "4") (pinfunction "VPWR_4") (pintype "bidirectional"))
      (node (ref "U5") (pin "6") (pinfunction "VPWR_6") (pintype "bidirectional"))
      (node (ref "U6") (pin "11") (pinfunction "VPWR_11") (pintype "bidirectional"))
      (node (ref "U6") (pin "31") (pinfunction "VPWR_31") (pintype "bidirectional"))
      (node (ref "U6") (pin "4") (pinfunction "VPWR_4") (pintype "bidirectional"))
      (node (ref "U6") (pin "6") (pinfunction "VPWR_6") (pintype "bidirectional"))
    )
    (net (code "36") (name "VCC") (class "Default")
      (node (ref "ARM") (pin "1") (pinfunction "1_1") (pintype "bidirectional"))
      (node (ref "C10") (pin "P$1") (pinfunction "P$1_P$1") (pintype "passive"))
      (node (ref "C11") (pin "P$1") (pinfunction "P$1_P$1") (pintype "passive"))
      (node (ref "C12") (pin "P$1") (pinfunction "P$1_P$1") (pintype "passive"))
      (node (ref "C4") (pin "P$1") (pinfunction "P$1_P$1") (pintype "passive"))
      (node (ref "C6") (pin "P$1") (pinfunction "P$1_P$1") (pintype "passive"))
      (node (ref "C7") (pin "P$1") (pinfunction "P$1_P$1") (pintype "passive"))
      (node (ref "C8") (pin "P$1") (pinfunction "P$1_P$1") (pintype "passive"))
      (node (ref "C9") (pin "P$1") (pinfunction "P$1_P$1") (pintype "passive"))
      (node (ref "J1") (pin "1") (pinfunction "1_1") (pintype "passive"))
      (node (ref "J6") (pin "6") (pinfunction "6_6") (pintype "passive"))
      (node (ref "L1") (pin "P$2") (pinfunction "P$2_P$2") (pintype "passive"))
      (node (ref "R1") (pin "P$2") (pinfunction "P$2_P$2") (pintype "passive"))
      (node (ref "R2") (pin "P$2") (pinfunction "P$2_P$2") (pintype "passive"))
      (node (ref "R3") (pin "P$2") (pinfunction "P$2_P$2") (pintype "passive"))
      (node (ref "R5") (pin "P$2") (pinfunction "P$2_P$2") (pintype "passive"))
      (node (ref "U2") (pin "4") (pinfunction "FB_4") (pintype "passive"))
      (node (ref "U3") (pin "1") (pinfunction "VBAT_1") (pintype "bidirectional"))
      (node (ref "U3") (pin "20") (pinfunction "VREF+_20") (pintype "bidirectional"))
      (node (ref "U3") (pin "21") (pinfunction "VDDA_21") (pintype "bidirectional"))
      (node (ref "U3") (pin "23") (pinfunction "VDD_1_23") (pintype "bidirectional"))
      (node (ref "U3") (pin "35") (pinfunction "VDD_2_35") (pintype "bidirectional"))
      (node (ref "U3") (pin "48") (pinfunction "VDD_3_48") (pintype "bidirectional"))
      (node (ref "U4") (pin "3") (pinfunction "VCC_3") (pintype "power_in"))
      (node (ref "U5") (pin "16") (pinfunction "D2/_16") (pintype "bidirectional"))
      (node (ref "U5") (pin "3") (pinfunction "SLEW_3") (pintype "bidirectional"))
      (node (ref "U6") (pin "16") (pinfunction "D2/_16") (pintype "bidirectional"))
      (node (ref "U6") (pin "3") (pinfunction "SLEW_3") (pintype "bidirectional"))
    )
    (net (code "37") (name "unconnected-(J6-Pad1)") (class "Default")
      (node (ref "J6") (pin "1") (pinfunction "1_1") (pintype "passive"))
    )
    (net (code "38") (name "unconnected-(U2-MODE-Pad5)") (class "Default")
      (node (ref "U2") (pin "5") (pinfunction "MODE_5") (pintype "passive"))
    )
    (net (code "39") (name "unconnected-(U2-RESET-Pad6)") (class "Default")
      (node (ref "U2") (pin "6") (pinfunction "RESET_6") (pintype "passive"))
    )
    (net (code "40") (name "unconnected-(U3-PA2-Pad10)") (class "Default")
      (node (ref "U3") (pin "10") (pinfunction "PA2_10") (pintype "bidirectional"))
    )
    (net (code "41") (name "unconnected-(U3-PA3-Pad11)") (class "Default")
      (node (ref "U3") (pin "11") (pinfunction "PA3_11") (pintype "bidirectional"))
    )
    (net (code "42") (name "unconnected-(U3-PA4-Pad12)") (class "Default")
      (node (ref "U3") (pin "12") (pinfunction "PA4_12") (pintype "bidirectional"))
    )
    (net (code "43") (name "unconnected-(U3-PA5-Pad13)") (class "Default")
      (node (ref "U3") (pin "13") (pinfunction "PA5_13") (pintype "bidirectional"))
    )
    (net (code "44") (name "unconnected-(U3-PA6-Pad14)") (class "Default")
      (node (ref "U3") (pin "14") (pinfunction "PA6_14") (pintype "bidirectional"))
    )
    (net (code "45") (name "unconnected-(U3-PA7-Pad15)") (class "Default")
      (node (ref "U3") (pin "15") (pinfunction "PA7_15") (pintype "bidirectional"))
    )
    (net (code "46") (name "unconnected-(U3-PA10-Pad32)") (class "Default")
      (node (ref "U3") (pin "32") (pinfunction "PA10_32") (pintype "bidirectional"))
    )
    (net (code "47") (name "unconnected-(U3-PA15-Pad38)") (class "Default")
      (node (ref "U3") (pin "38") (pinfunction "PA15_38") (pintype "bidirectional"))
    )
    (net (code "48") (name "unconnected-(U3-PB0-Pad17)") (class "Default")
      (node (ref "U3") (pin "17") (pinfunction "PB0_17") (pintype "bidirectional"))
    )
    (net (code "49") (name "unconnected-(U3-PB1-Pad18)") (class "Default")
      (node (ref "U3") (pin "18") (pinfunction "PB1_18") (pintype "bidirectional"))
    )
    (net (code "50") (name "unconnected-(U3-PB2-Pad19)") (class "Default")
      (node (ref "U3") (pin "19") (pinfunction "PB2_19") (pintype "bidirectional"))
    )
    (net (code "51") (name "unconnected-(U3-PB8-BOOT0-Pad46)") (class "Default")
      (node (ref "U3") (pin "46") (pinfunction "PB8-BOOT0_46") (pintype "bidirectional"))
    )
    (net (code "52") (name "unconnected-(U3-PB10-Pad22)") (class "Default")
      (node (ref "U3") (pin "22") (pinfunction "PB10_22") (pintype "bidirectional"))
    )
    (net (code "53") (name "unconnected-(U3-PB11-Pad24)") (class "Default")
      (node (ref "U3") (pin "24") (pinfunction "PB11_24") (pintype "bidirectional"))
    )
    (net (code "54") (name "unconnected-(U3-PB13-Pad26)") (class "Default")
      (node (ref "U3") (pin "26") (pinfunction "PB13_26") (pintype "bidirectional"))
    )
    (net (code "55") (name "unconnected-(U3-PB14-Pad27)") (class "Default")
      (node (ref "U3") (pin "27") (pinfunction "PB14_27") (pintype "bidirectional"))
    )
    (net (code "56") (name "unconnected-(U3-PB15-Pad28)") (class "Default")
      (node (ref "U3") (pin "28") (pinfunction "PB15_28") (pintype "bidirectional"))
    )
    (net (code "57") (name "unconnected-(U3-PC4-Pad16)") (class "Default")
      (node (ref "U3") (pin "16") (pinfunction "PC4_16") (pintype "bidirectional"))
    )
    (net (code "58") (name "unconnected-(U3-PC6-Pad29)") (class "Default")
      (node (ref "U3") (pin "29") (pinfunction "PC6_29") (pintype "bidirectional"))
    )
    (net (code "59") (name "unconnected-(U3-PC10-Pad39)") (class "Default")
      (node (ref "U3") (pin "39") (pinfunction "PC10_39") (pintype "bidirectional"))
    )
    (net (code "60") (name "unconnected-(U3-PC11-Pad40)") (class "Default")
      (node (ref "U3") (pin "40") (pinfunction "PC11_40") (pintype "bidirectional"))
    )
    (net (code "61") (name "unconnected-(U3-PC14-OSC32_IN-Pad3)") (class "Default")
      (node (ref "U3") (pin "3") (pinfunction "PC14-OSC32_IN_3") (pintype "bidirectional"))
    )
    (net (code "62") (name "unconnected-(U3-PC15-OSC32_OUT-Pad4)") (class "Default")
      (node (ref "U3") (pin "4") (pinfunction "PC15-OSC32_OUT_4") (pintype "bidirectional"))
    )
    (net (code "63") (name "unconnected-(U5-INV-Pad7)") (class "Default")
      (node (ref "U5") (pin "7") (pinfunction "INV_7") (pintype "bidirectional"))
    )
    (net (code "64") (name "unconnected-(U6-INV-Pad7)") (class "Default")
      (node (ref "U6") (pin "7") (pinfunction "INV_7") (pintype "bidirectional"))
    )
  )
)
